# slave.net
KiCad netlist of a schematic drawn in EAGLE
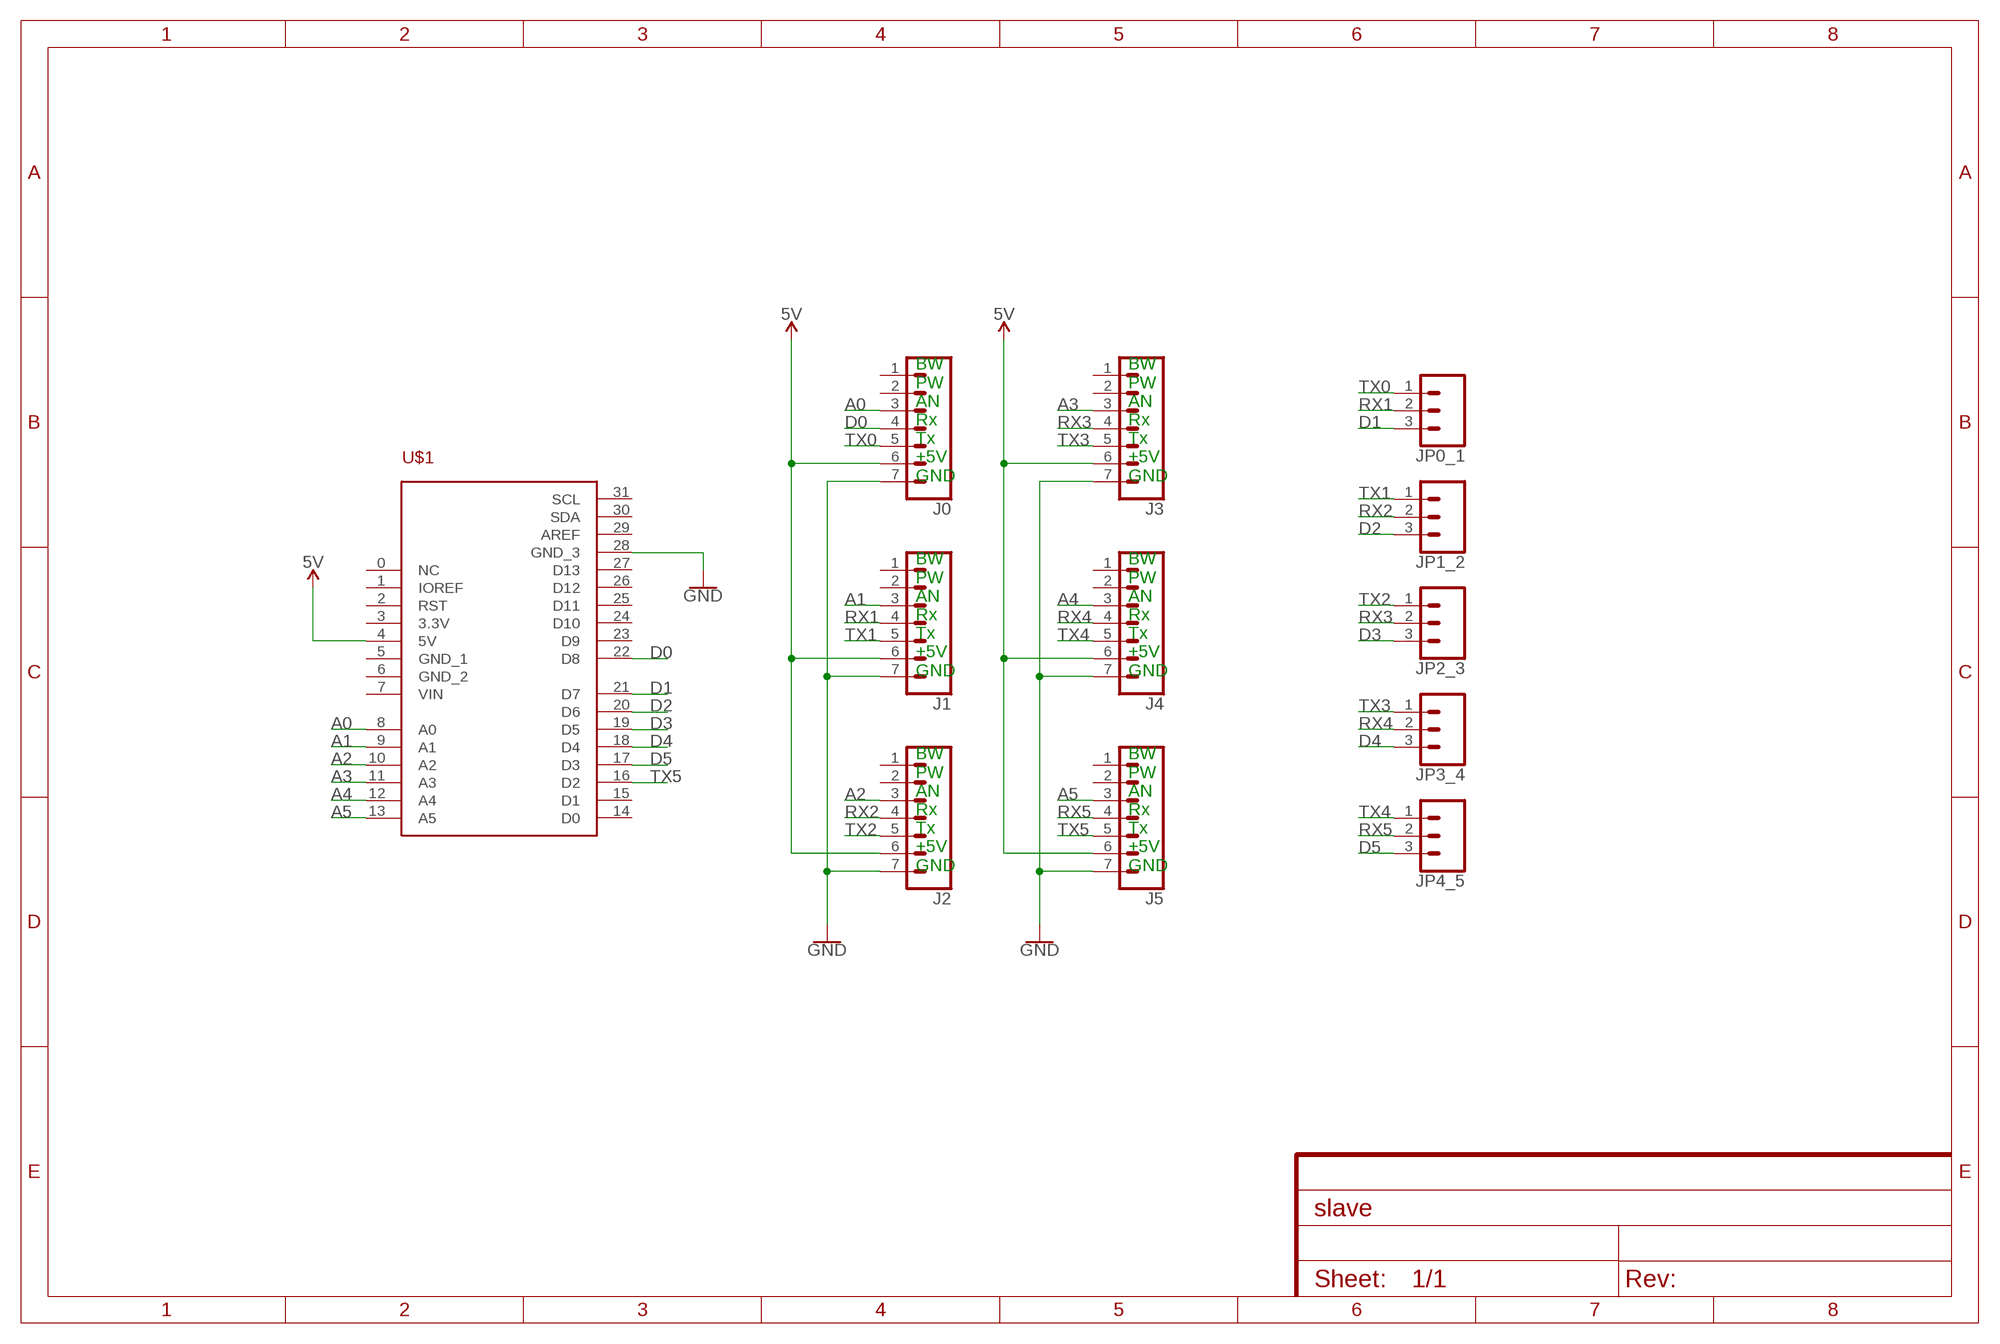
[diagram p0: schematic, sheet 1]

(export (version "E")
  (design (tool "Eeschema 10.0.6"))
  (components
    (comp (ref "J0")
      (value "CONN_07LONGPADS")
      (footprint "eagle-import:1X07_LONGPADS")
      (libsource (lib "eagle-import") (part "CONN_07LONGPADS"))
    )
    (comp (ref "J1")
      (value "CONN_07LONGPADS")
      (footprint "eagle-import:1X07_LONGPADS")
      (libsource (lib "eagle-import") (part "CONN_07LONGPADS"))
    )
    (comp (ref "J2")
      (value "CONN_07LONGPADS")
      (footprint "eagle-import:1X07_LONGPADS")
      (libsource (lib "eagle-import") (part "CONN_07LONGPADS"))
    )
    (comp (ref "J3")
      (value "CONN_07LONGPADS")
      (footprint "eagle-import:1X07_LONGPADS")
      (libsource (lib "eagle-import") (part "CONN_07LONGPADS"))
    )
    (comp (ref "J4")
      (value "CONN_07LONGPADS")
      (footprint "eagle-import:1X07_LONGPADS")
      (libsource (lib "eagle-import") (part "CONN_07LONGPADS"))
    )
    (comp (ref "J5")
      (value "CONN_07LONGPADS")
      (footprint "eagle-import:1X07_LONGPADS")
      (libsource (lib "eagle-import") (part "CONN_07LONGPADS"))
    )
    (comp (ref "JP0_1")
      (value "CONN_03LONGPADS")
      (footprint "eagle-import:1X03_LONGPADS")
      (libsource (lib "eagle-import") (part "CONN_03LONGPADS"))
    )
    (comp (ref "JP1_2")
      (value "CONN_03LONGPADS")
      (footprint "eagle-import:1X03_LONGPADS")
      (libsource (lib "eagle-import") (part "CONN_03LONGPADS"))
    )
    (comp (ref "JP2_3")
      (value "CONN_03LONGPADS")
      (footprint "eagle-import:1X03_LONGPADS")
      (libsource (lib "eagle-import") (part "CONN_03LONGPADS"))
    )
    (comp (ref "JP3_4")
      (value "CONN_03LONGPADS")
      (footprint "eagle-import:1X03_LONGPADS")
      (libsource (lib "eagle-import") (part "CONN_03LONGPADS"))
    )
    (comp (ref "JP4_5")
      (value "CONN_03LONGPADS")
      (footprint "eagle-import:1X03_LONGPADS")
      (libsource (lib "eagle-import") (part "CONN_03LONGPADS"))
    )
    (comp (ref "U$1")
      (value "ARDUINO_UNO_STACK")
      (footprint "eagle-import:ARDUINO_UNO_STACK")
      (libsource (lib "eagle-import") (part "ARDUINO_UNO_STACK"))
    )
  )
  (nets
    (net (code "1") (name "/3.3V") (class "Default")
      (node (ref "U$1") (pin "3") (pinfunction "3.3V_3") (pintype "power_in"))
    )
    (net (code "2") (name "/A0") (class "Default")
      (node (ref "J0") (pin "3") (pinfunction "3_3") (pintype "passive"))
      (node (ref "U$1") (pin "8") (pinfunction "A0_8") (pintype "bidirectional"))
    )
    (net (code "3") (name "/A1") (class "Default")
      (node (ref "J1") (pin "3") (pinfunction "3_3") (pintype "passive"))
      (node (ref "U$1") (pin "9") (pinfunction "A1_9") (pintype "bidirectional"))
    )
    (net (code "4") (name "/A2") (class "Default")
      (node (ref "J2") (pin "3") (pinfunction "3_3") (pintype "passive"))
      (node (ref "U$1") (pin "10") (pinfunction "A2_10") (pintype "bidirectional"))
    )
    (net (code "5") (name "/A3") (class "Default")
      (node (ref "J3") (pin "3") (pinfunction "3_3") (pintype "passive"))
      (node (ref "U$1") (pin "11") (pinfunction "A3_11") (pintype "bidirectional"))
    )
    (net (code "6") (name "/A4") (class "Default")
      (node (ref "J4") (pin "3") (pinfunction "3_3") (pintype "passive"))
      (node (ref "U$1") (pin "12") (pinfunction "A4_12") (pintype "bidirectional"))
    )
    (net (code "7") (name "/A5") (class "Default")
      (node (ref "J5") (pin "3") (pinfunction "3_3") (pintype "passive"))
      (node (ref "U$1") (pin "13") (pinfunction "A5_13") (pintype "bidirectional"))
    )
    (net (code "8") (name "/D0") (class "Default")
      (node (ref "J0") (pin "4") (pinfunction "4_4") (pintype "passive"))
      (node (ref "U$1") (pin "22") (pinfunction "D8_22") (pintype "bidirectional"))
    )
    (net (code "9") (name "/D1") (class "Default")
      (node (ref "JP0_1") (pin "3") (pinfunction "3_3") (pintype "passive"))
      (node (ref "U$1") (pin "21") (pinfunction "D7_21") (pintype "bidirectional"))
    )
    (net (code "10") (name "/D2") (class "Default")
      (node (ref "JP1_2") (pin "3") (pinfunction "3_3") (pintype "passive"))
      (node (ref "U$1") (pin "20") (pinfunction "D6_20") (pintype "bidirectional"))
    )
    (net (code "11") (name "/D3") (class "Default")
      (node (ref "JP2_3") (pin "3") (pinfunction "3_3") (pintype "passive"))
      (node (ref "U$1") (pin "19") (pinfunction "D5_19") (pintype "bidirectional"))
    )
    (net (code "12") (name "/D4") (class "Default")
      (node (ref "JP3_4") (pin "3") (pinfunction "3_3") (pintype "passive"))
      (node (ref "U$1") (pin "18") (pinfunction "D4_18") (pintype "bidirectional"))
    )
    (net (code "13") (name "/D5") (class "Default")
      (node (ref "JP4_5") (pin "3") (pinfunction "3_3") (pintype "passive"))
      (node (ref "U$1") (pin "17") (pinfunction "D3_17") (pintype "bidirectional"))
    )
    (net (code "14") (name "/GND_1") (class "Default")
      (node (ref "U$1") (pin "5") (pinfunction "GND_1_5") (pintype "power_in"))
    )
    (net (code "15") (name "/GND_2") (class "Default")
      (node (ref "U$1") (pin "6") (pinfunction "GND_2_6") (pintype "power_in"))
    )
    (net (code "16") (name "/RX1") (class "Default")
      (node (ref "J1") (pin "4") (pinfunction "4_4") (pintype "passive"))
      (node (ref "JP0_1") (pin "2") (pinfunction "2_2") (pintype "passive"))
    )
    (net (code "17") (name "/RX2") (class "Default")
      (node (ref "J2") (pin "4") (pinfunction "4_4") (pintype "passive"))
      (node (ref "JP1_2") (pin "2") (pinfunction "2_2") (pintype "passive"))
    )
    (net (code "18") (name "/RX3") (class "Default")
      (node (ref "J3") (pin "4") (pinfunction "4_4") (pintype "passive"))
      (node (ref "JP2_3") (pin "2") (pinfunction "2_2") (pintype "passive"))
    )
    (net (code "19") (name "/RX4") (class "Default")
      (node (ref "J4") (pin "4") (pinfunction "4_4") (pintype "passive"))
      (node (ref "JP3_4") (pin "2") (pinfunction "2_2") (pintype "passive"))
    )
    (net (code "20") (name "/RX5") (class "Default")
      (node (ref "J5") (pin "4") (pinfunction "4_4") (pintype "passive"))
      (node (ref "JP4_5") (pin "2") (pinfunction "2_2") (pintype "passive"))
    )
    (net (code "21") (name "/TX0") (class "Default")
      (node (ref "J0") (pin "5") (pinfunction "5_5") (pintype "passive"))
      (node (ref "JP0_1") (pin "1") (pinfunction "1_1") (pintype "passive"))
    )
    (net (code "22") (name "/TX1") (class "Default")
      (node (ref "J1") (pin "5") (pinfunction "5_5") (pintype "passive"))
      (node (ref "JP1_2") (pin "1") (pinfunction "1_1") (pintype "passive"))
    )
    (net (code "23") (name "/TX2") (class "Default")
      (node (ref "J2") (pin "5") (pinfunction "5_5") (pintype "passive"))
      (node (ref "JP2_3") (pin "1") (pinfunction "1_1") (pintype "passive"))
    )
    (net (code "24") (name "/TX3") (class "Default")
      (node (ref "J3") (pin "5") (pinfunction "5_5") (pintype "passive"))
      (node (ref "JP3_4") (pin "1") (pinfunction "1_1") (pintype "passive"))
    )
    (net (code "25") (name "/TX4") (class "Default")
      (node (ref "J4") (pin "5") (pinfunction "5_5") (pintype "passive"))
      (node (ref "JP4_5") (pin "1") (pinfunction "1_1") (pintype "passive"))
    )
    (net (code "26") (name "/TX5") (class "Default")
      (node (ref "J5") (pin "5") (pinfunction "5_5") (pintype "passive"))
      (node (ref "U$1") (pin "16") (pinfunction "D2_16") (pintype "bidirectional"))
    )
    (net (code "27") (name "/VIN") (class "Default")
      (node (ref "U$1") (pin "7") (pinfunction "VIN_7") (pintype "power_in"))
    )
    (net (code "28") (name "5V") (class "Default")
      (node (ref "J0") (pin "6") (pinfunction "6_6") (pintype "passive"))
      (node (ref "J1") (pin "6") (pinfunction "6_6") (pintype "passive"))
      (node (ref "J2") (pin "6") (pinfunction "6_6") (pintype "passive"))
      (node (ref "J3") (pin "6") (pinfunction "6_6") (pintype "passive"))
      (node (ref "J4") (pin "6") (pinfunction "6_6") (pintype "passive"))
      (node (ref "J5") (pin "6") (pinfunction "6_6") (pintype "passive"))
      (node (ref "U$1") (pin "4") (pinfunction "5V_4") (pintype "power_in"))
    )
    (net (code "29") (name "GND") (class "Default")
      (node (ref "J0") (pin "7") (pinfunction "7_7") (pintype "passive"))
      (node (ref "J1") (pin "7") (pinfunction "7_7") (pintype "passive"))
      (node (ref "J2") (pin "7") (pinfunction "7_7") (pintype "passive"))
      (node (ref "J3") (pin "7") (pinfunction "7_7") (pintype "passive"))
      (node (ref "J4") (pin "7") (pinfunction "7_7") (pintype "passive"))
      (node (ref "J5") (pin "7") (pinfunction "7_7") (pintype "passive"))
      (node (ref "U$1") (pin "28") (pinfunction "GND_3_28") (pintype "power_in"))
    )
    (net (code "30") (name "unconnected-(J0-Pad1)") (class "Default")
      (node (ref "J0") (pin "1") (pinfunction "1_1") (pintype "passive"))
    )
    (net (code "31") (name "unconnected-(J0-Pad2)") (class "Default")
      (node (ref "J0") (pin "2") (pinfunction "2_2") (pintype "passive"))
    )
    (net (code "32") (name "unconnected-(J1-Pad1)") (class "Default")
      (node (ref "J1") (pin "1") (pinfunction "1_1") (pintype "passive"))
    )
    (net (code "33") (name "unconnected-(J1-Pad2)") (class "Default")
      (node (ref "J1") (pin "2") (pinfunction "2_2") (pintype "passive"))
    )
    (net (code "34") (name "unconnected-(J2-Pad1)") (class "Default")
      (node (ref "J2") (pin "1") (pinfunction "1_1") (pintype "passive"))
    )
    (net (code "35") (name "unconnected-(J2-Pad2)") (class "Default")
      (node (ref "J2") (pin "2") (pinfunction "2_2") (pintype "passive"))
    )
    (net (code "36") (name "unconnected-(J3-Pad1)") (class "Default")
      (node (ref "J3") (pin "1") (pinfunction "1_1") (pintype "passive"))
    )
    (net (code "37") (name "unconnected-(J3-Pad2)") (class "Default")
      (node (ref "J3") (pin "2") (pinfunction "2_2") (pintype "passive"))
    )
    (net (code "38") (name "unconnected-(J4-Pad1)") (class "Default")
      (node (ref "J4") (pin "1") (pinfunction "1_1") (pintype "passive"))
    )
    (net (code "39") (name "unconnected-(J4-Pad2)") (class "Default")
      (node (ref "J4") (pin "2") (pinfunction "2_2") (pintype "passive"))
    )
    (net (code "40") (name "unconnected-(J5-Pad1)") (class "Default")
      (node (ref "J5") (pin "1") (pinfunction "1_1") (pintype "passive"))
    )
    (net (code "41") (name "unconnected-(J5-Pad2)") (class "Default")
      (node (ref "J5") (pin "2") (pinfunction "2_2") (pintype "passive"))
    )
    (net (code "42") (name "unconnected-(U$1-AREF-Pad29)") (class "Default")
      (node (ref "U$1") (pin "29") (pinfunction "AREF_29") (pintype "bidirectional"))
    )
    (net (code "43") (name "unconnected-(U$1-D0-Pad14)") (class "Default")
      (node (ref "U$1") (pin "14") (pinfunction "D0_14") (pintype "bidirectional"))
    )
    (net (code "44") (name "unconnected-(U$1-D1-Pad15)") (class "Default")
      (node (ref "U$1") (pin "15") (pinfunction "D1_15") (pintype "bidirectional"))
    )
    (net (code "45") (name "unconnected-(U$1-D9-Pad23)") (class "Default")
      (node (ref "U$1") (pin "23") (pinfunction "D9_23") (pintype "bidirectional"))
    )
    (net (code "46") (name "unconnected-(U$1-D10-Pad24)") (class "Default")
      (node (ref "U$1") (pin "24") (pinfunction "D10_24") (pintype "bidirectional"))
    )
    (net (code "47") (name "unconnected-(U$1-D11-Pad25)") (class "Default")
      (node (ref "U$1") (pin "25") (pinfunction "D11_25") (pintype "bidirectional"))
    )
    (net (code "48") (name "unconnected-(U$1-D12-Pad26)") (class "Default")
      (node (ref "U$1") (pin "26") (pinfunction "D12_26") (pintype "bidirectional"))
    )
    (net (code "49") (name "unconnected-(U$1-D13-Pad27)") (class "Default")
      (node (ref "U$1") (pin "27") (pinfunction "D13_27") (pintype "bidirectional"))
    )
    (net (code "50") (name "unconnected-(U$1-IOREF-Pad1)") (class "Default")
      (node (ref "U$1") (pin "1") (pinfunction "IOREF_1") (pintype "bidirectional"))
    )
    (net (code "51") (name "unconnected-(U$1-NC-Pad0)") (class "Default")
      (node (ref "U$1") (pin "0") (pinfunction "NC_0") (pintype "bidirectional"))
    )
    (net (code "52") (name "unconnected-(U$1-RST-Pad2)") (class "Default")
      (node (ref "U$1") (pin "2") (pinfunction "RST_2") (pintype "bidirectional"))
    )
    (net (code "53") (name "unconnected-(U$1-SCL-Pad31)") (class "Default")
      (node (ref "U$1") (pin "31") (pinfunction "SCL_31") (pintype "bidirectional"))
    )
    (net (code "54") (name "unconnected-(U$1-SDA-Pad30)") (class "Default")
      (node (ref "U$1") (pin "30") (pinfunction "SDA_30") (pintype "bidirectional"))
    )
  )
)
